# lorelei_B_v1_1.net
KiCad netlist of a schematic drawn in EAGLE
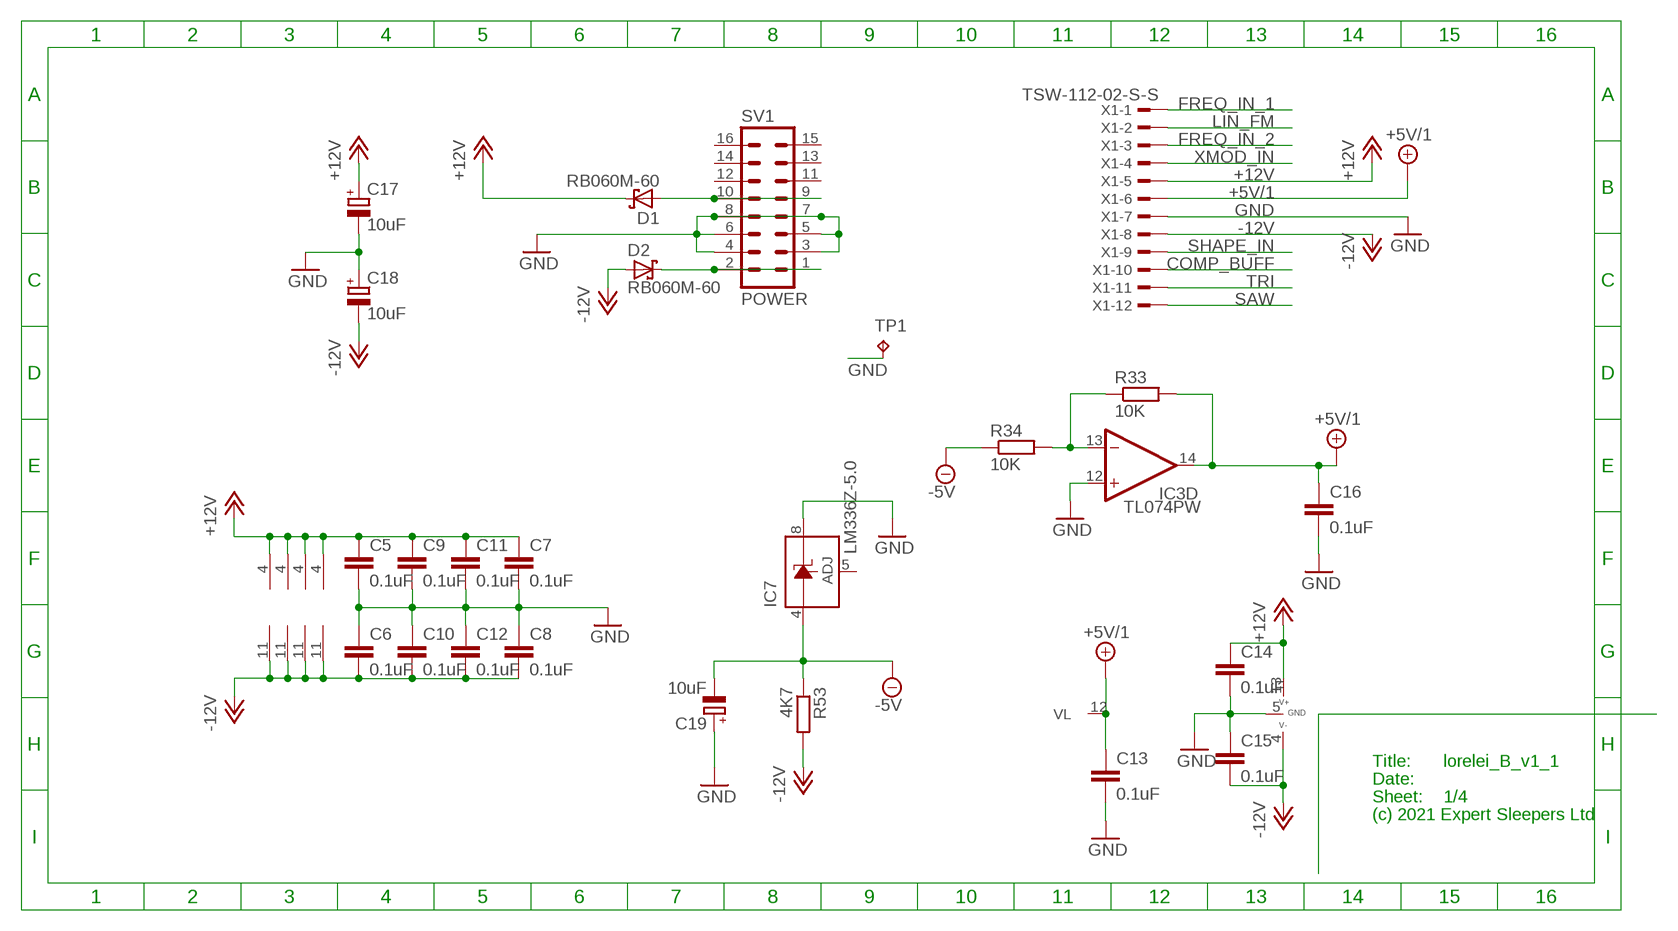
[diagram p0: schematic, sheet 1]
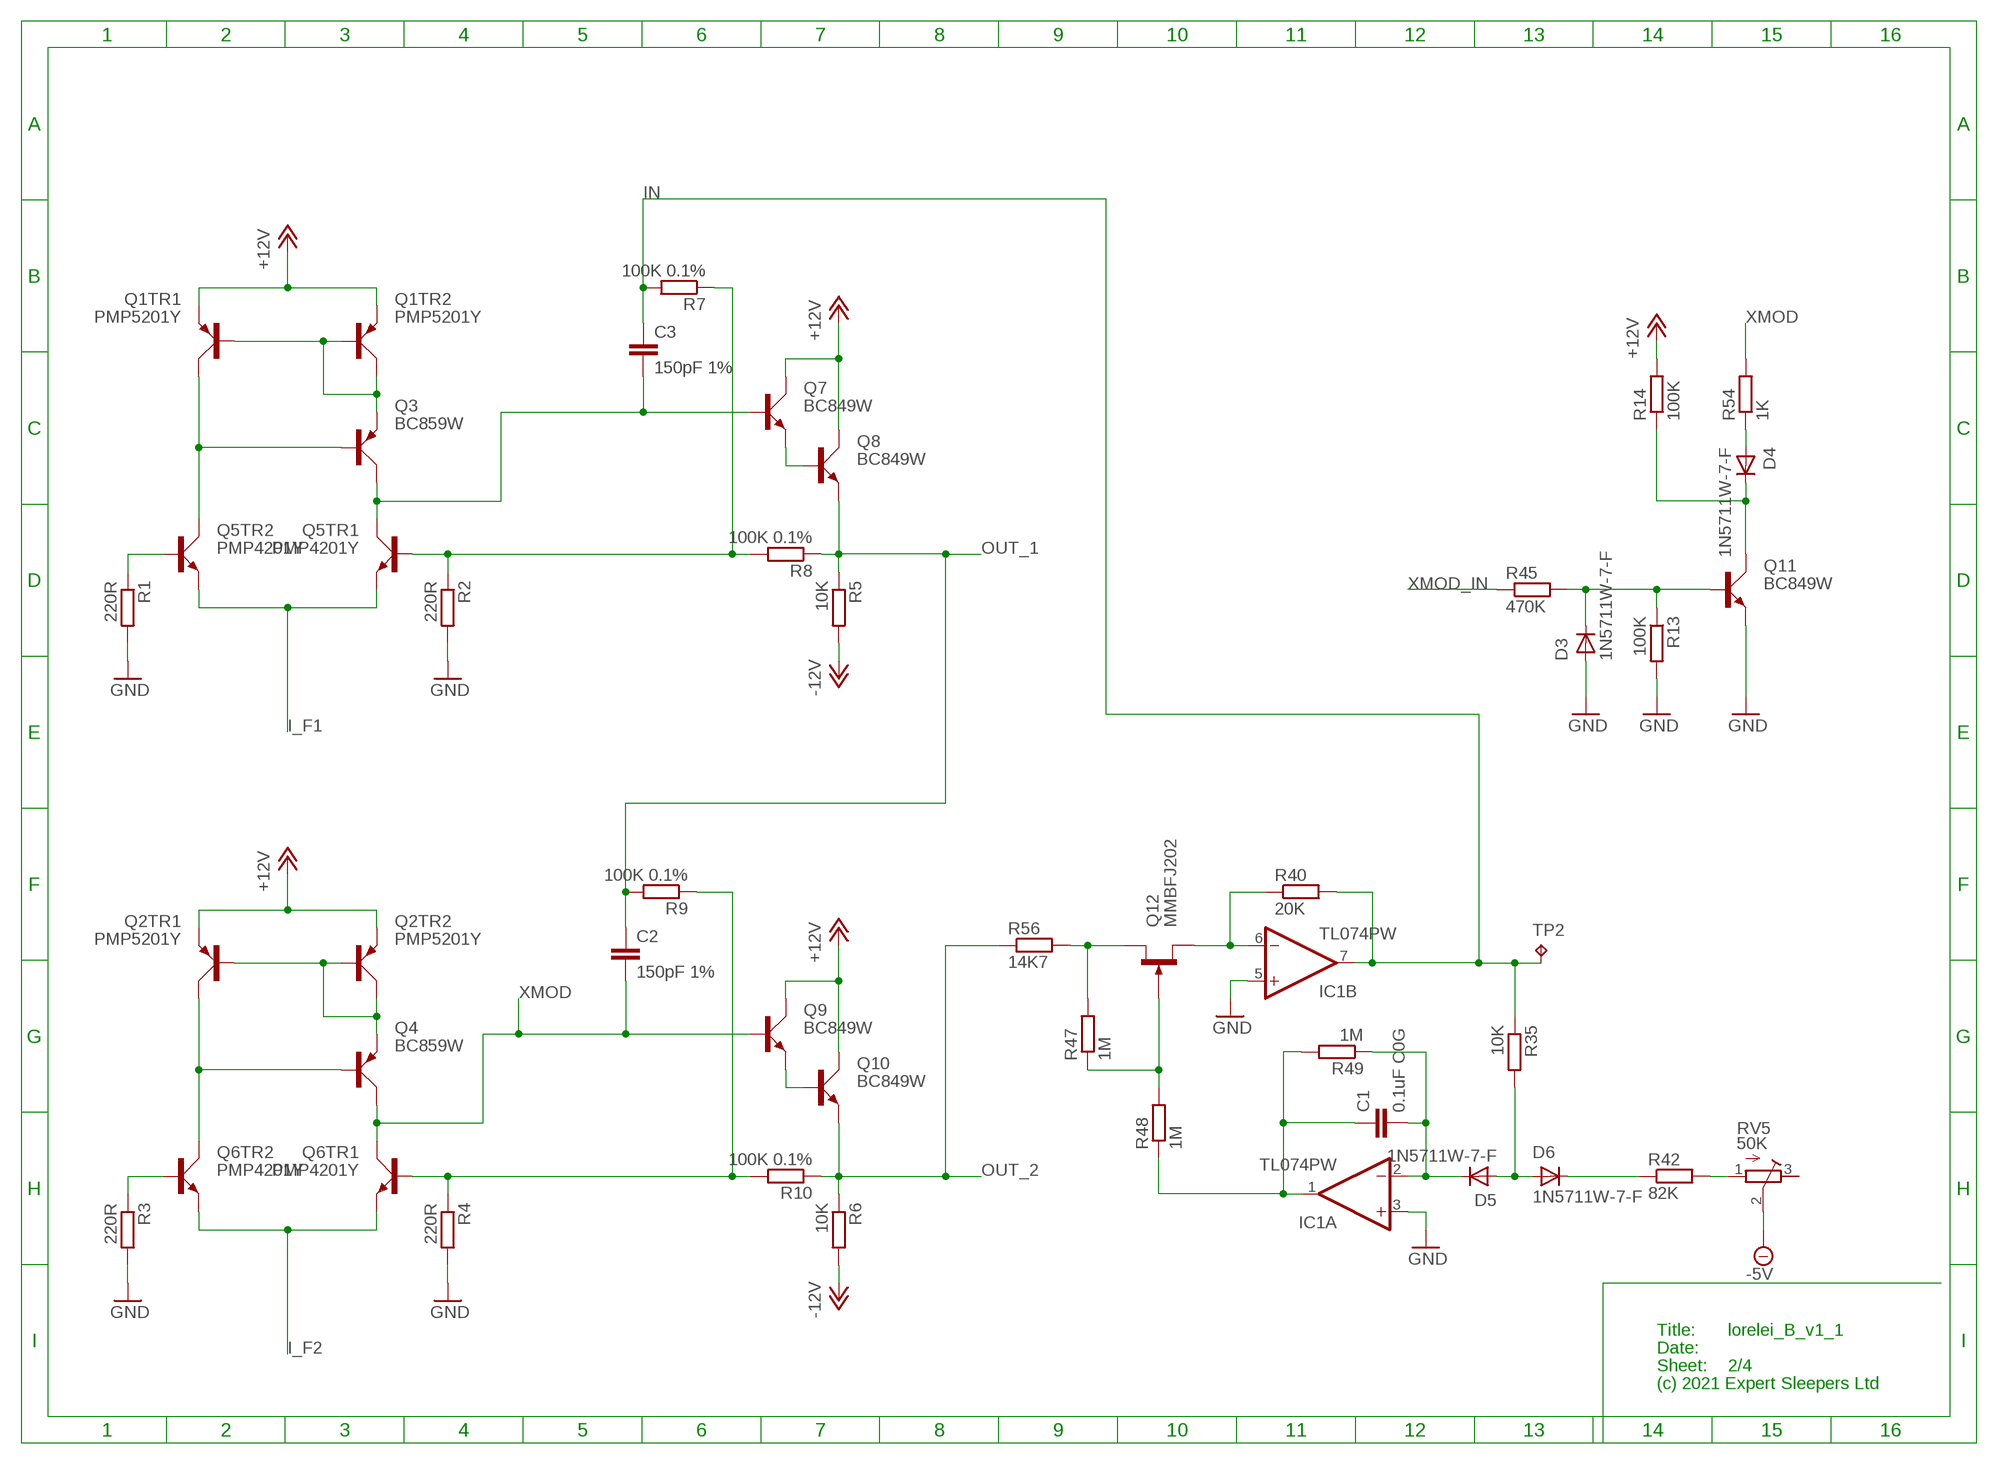
[diagram p1: schematic, sheet 2]
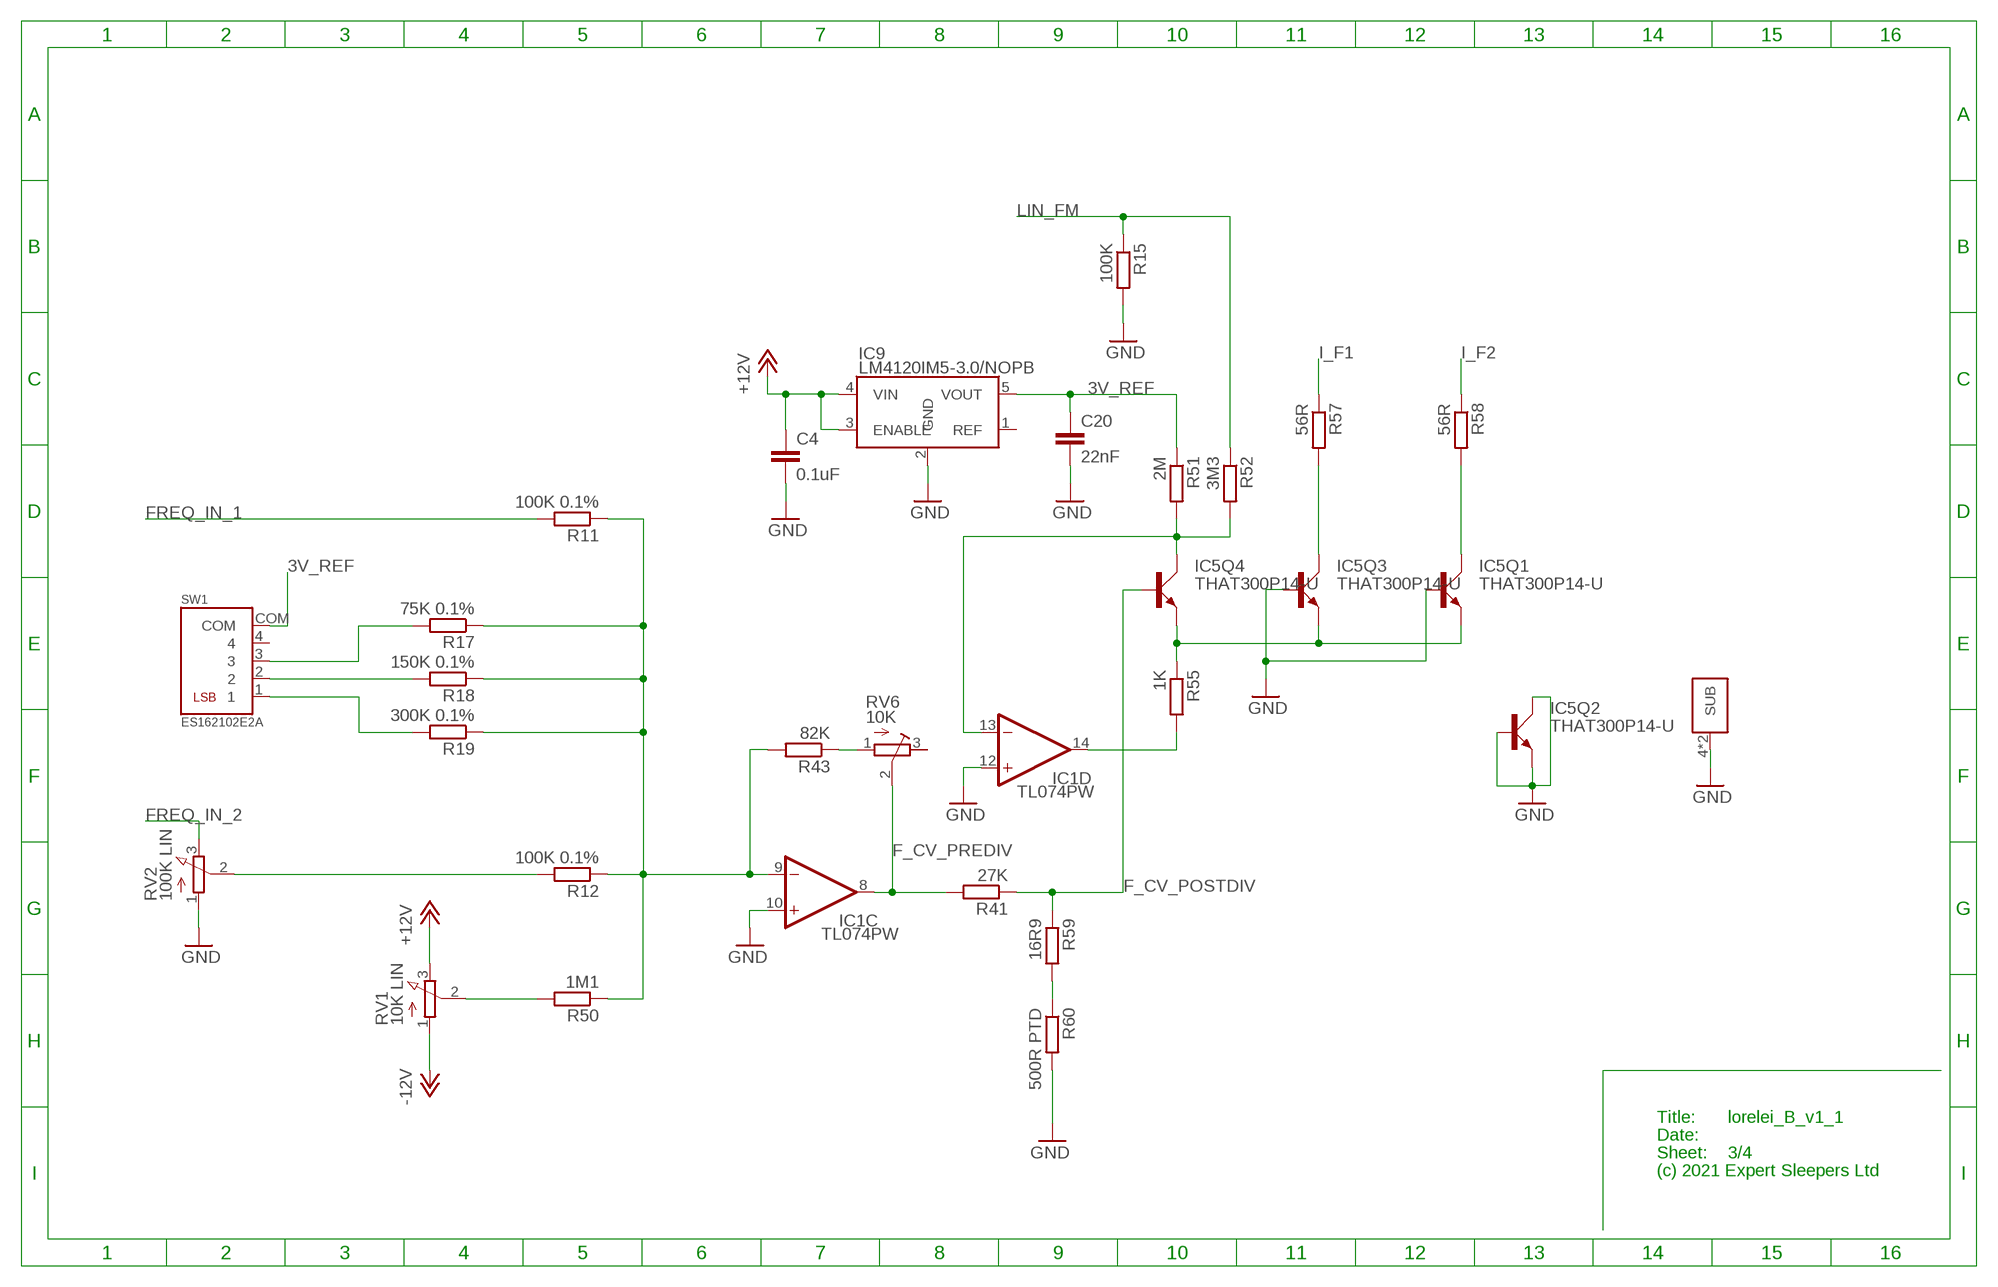
[diagram p2: schematic, sheet 3]
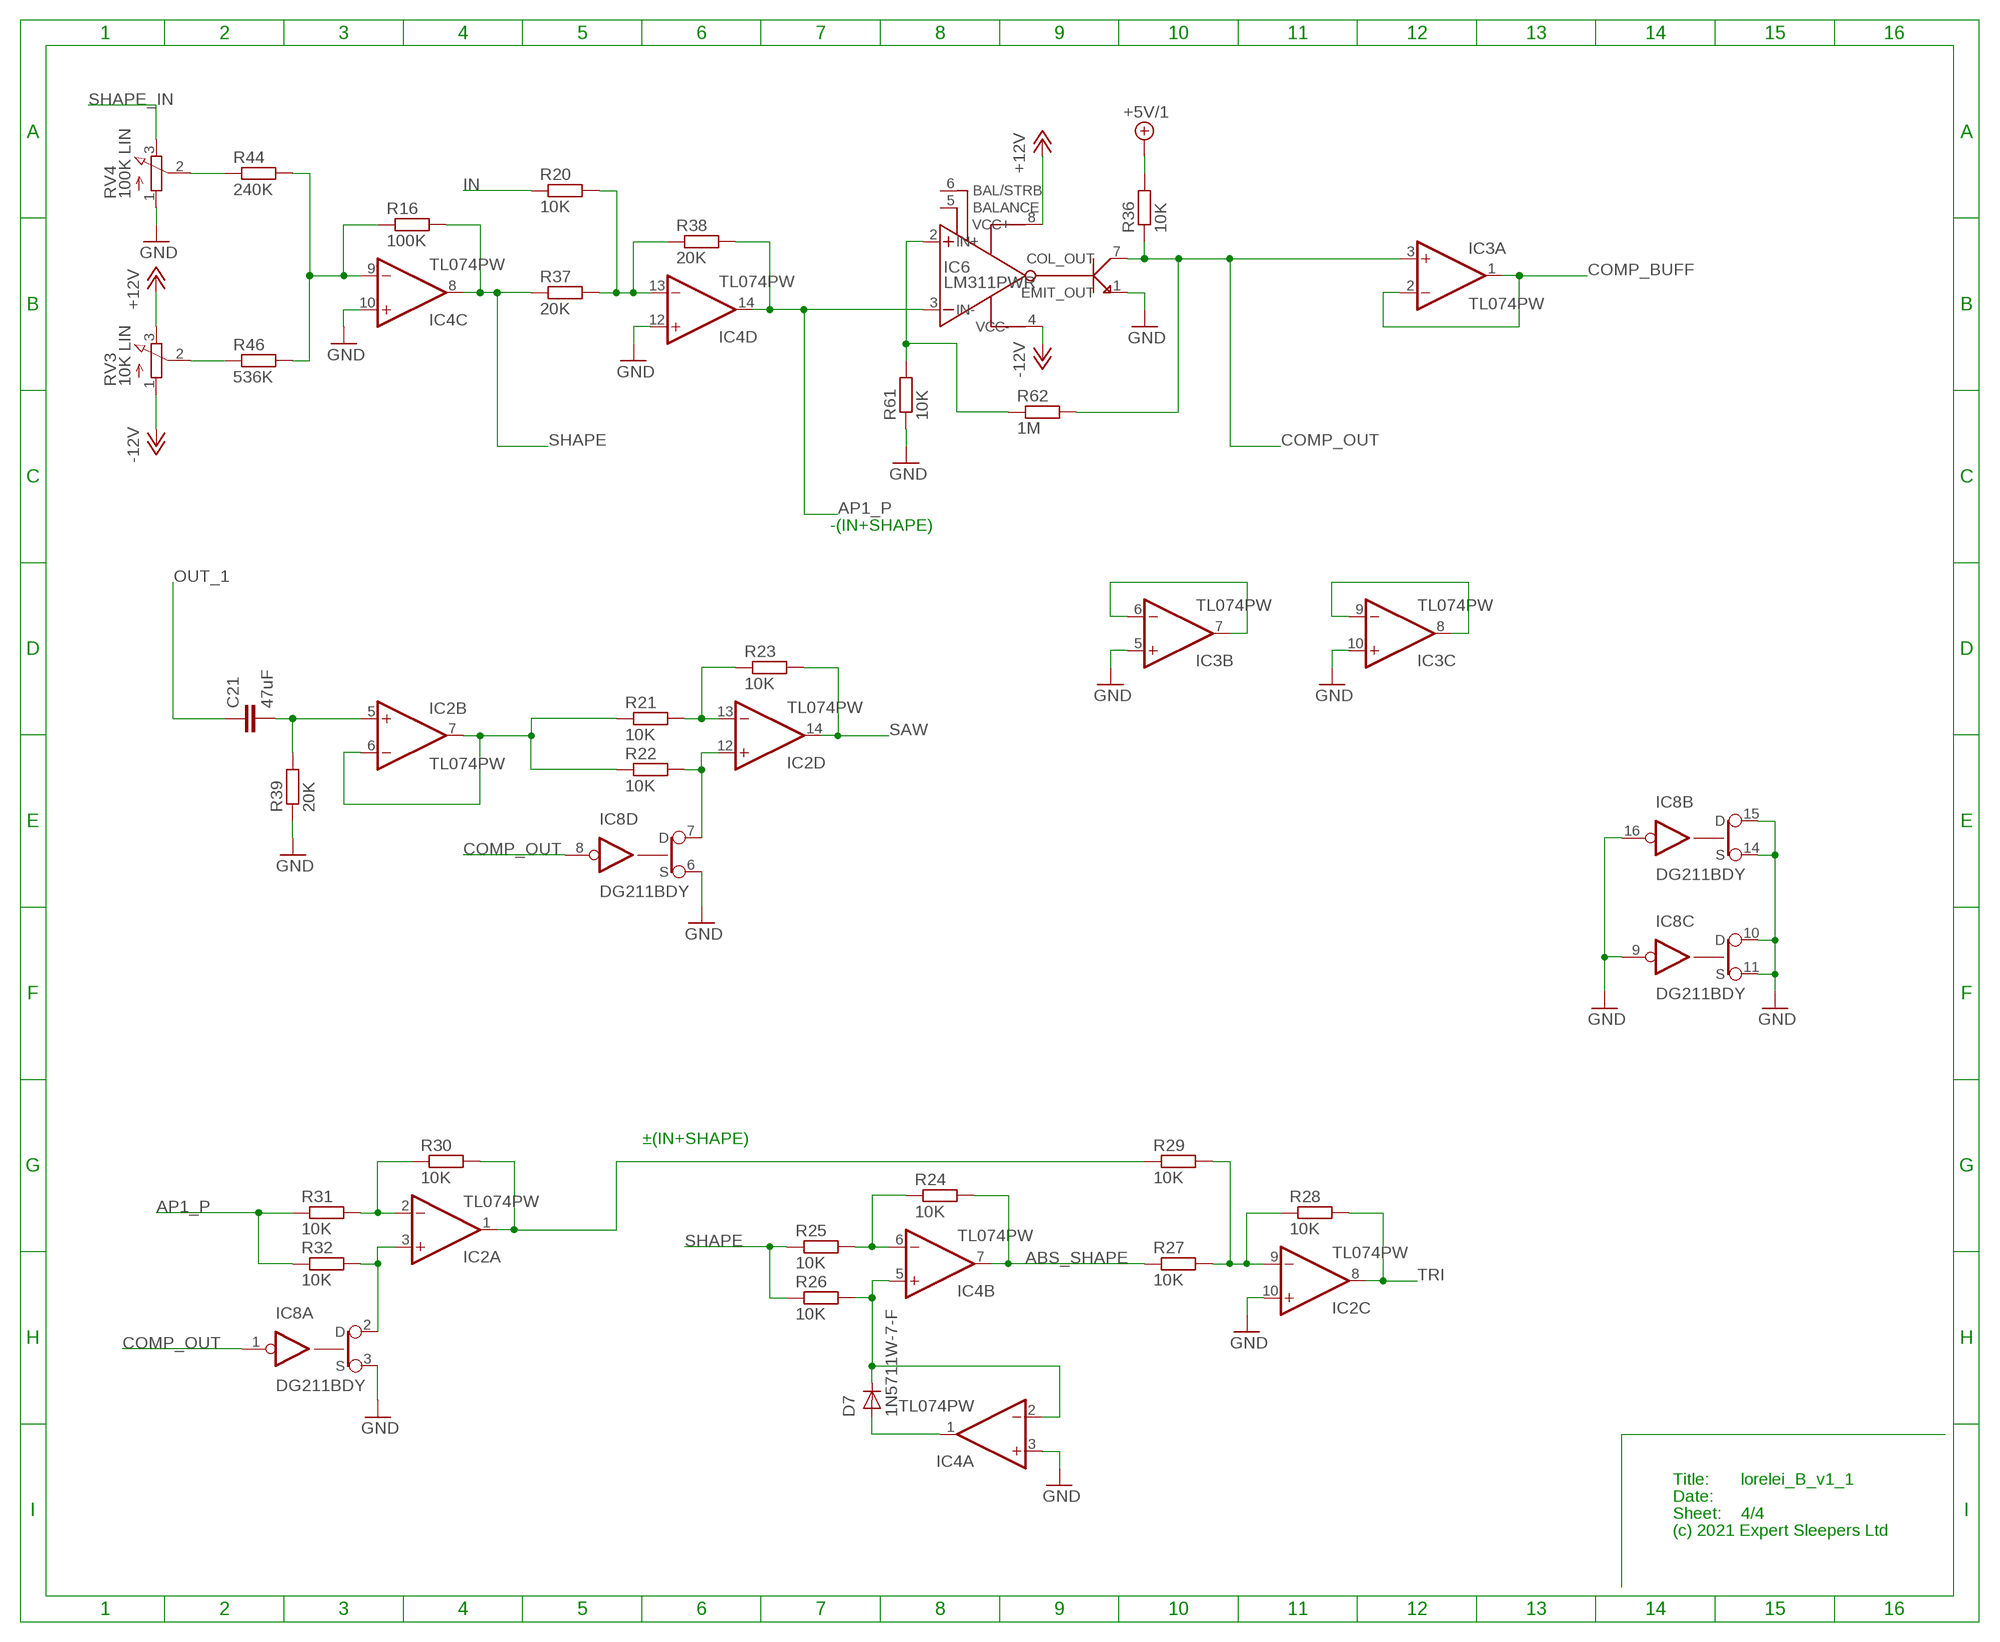
[diagram p3: schematic, sheet 4]

(export (version "E")
  (design (tool "Eeschema 10.0.6"))
  (components
    (comp (ref "C4")
      (value "0.1uF")
      (footprint "eagle-import:C0402")
      (libsource (lib "eagle-import") (part "C-EUC0402"))
    )
    (comp (ref "C20")
      (value "22nF")
      (footprint "eagle-import:C0402")
      (libsource (lib "eagle-import") (part "C-EUC0402"))
    )
    (comp (ref "IC1")
      (value "TL074PW")
      (footprint "eagle-import:PW_R-PDSO-G14")
      (libsource (lib "eagle-import") (part "TL074PW"))
    )
    (comp (ref "IC5")
      (value "THAT300P14-U")
      (footprint "eagle-import:DIL14")
      (libsource (lib "eagle-import") (part "THAT300P14-U"))
    )
    (comp (ref "IC9")
      (value "LM4120IM5-3.0/NOPB")
      (footprint "eagle-import:SOT95P280X145-5N")
      (fields
        (field (name "ARROW_PART_NUMBER") "LM4120IM5-5.0/NOPB")
        (field (name "MOUSER_PART_NUMBER") "926-LM4120IM550NOPB")
      )
      (libsource (lib "eagle-import") (part "LM4120IM5-5.0_NOPB"))
    )
    (comp (ref "R11")
      (value "100K 0.1%")
      (footprint "eagle-import:R0603")
      (libsource (lib "eagle-import") (part "R-EU_R0603"))
    )
    (comp (ref "R12")
      (value "100K 0.1%")
      (footprint "eagle-import:R0603")
      (libsource (lib "eagle-import") (part "R-EU_R0603"))
    )
    (comp (ref "R15")
      (value "100K")
      (footprint "eagle-import:R0603")
      (libsource (lib "eagle-import") (part "R-EU_R0603"))
    )
    (comp (ref "R17")
      (value "75K 0.1%")
      (footprint "eagle-import:R0603")
      (libsource (lib "eagle-import") (part "R-EU_R0603"))
    )
    (comp (ref "R18")
      (value "150K 0.1%")
      (footprint "eagle-import:R0603")
      (libsource (lib "eagle-import") (part "R-EU_R0603"))
    )
    (comp (ref "R19")
      (value "300K 0.1%")
      (footprint "eagle-import:R0603")
      (libsource (lib "eagle-import") (part "R-EU_R0603"))
    )
    (comp (ref "R41")
      (value "27K")
      (footprint "eagle-import:R0603")
      (libsource (lib "eagle-import") (part "R-EU_R0603"))
    )
    (comp (ref "R43")
      (value "82K")
      (footprint "eagle-import:R0603")
      (libsource (lib "eagle-import") (part "R-EU_R0603"))
    )
    (comp (ref "R50")
      (value "1M1")
      (footprint "eagle-import:R0603")
      (libsource (lib "eagle-import") (part "R-EU_R0603"))
    )
    (comp (ref "R51")
      (value "2M")
      (footprint "eagle-import:R0603")
      (libsource (lib "eagle-import") (part "R-EU_R0603"))
    )
    (comp (ref "R52")
      (value "3M3")
      (footprint "eagle-import:R0603")
      (libsource (lib "eagle-import") (part "R-EU_R0603"))
    )
    (comp (ref "R55")
      (value "1K")
      (footprint "eagle-import:R0603")
      (libsource (lib "eagle-import") (part "R-EU_R0603"))
    )
    (comp (ref "R57")
      (value "56R")
      (footprint "eagle-import:R0603")
      (libsource (lib "eagle-import") (part "R-EU_R0603"))
    )
    (comp (ref "R58")
      (value "56R")
      (footprint "eagle-import:R0603")
      (libsource (lib "eagle-import") (part "R-EU_R0603"))
    )
    (comp (ref "R59")
      (value "16R9")
      (footprint "eagle-import:R0603")
      (libsource (lib "eagle-import") (part "R-EU_R0603"))
    )
    (comp (ref "R60")
      (value "500R PTD")
      (footprint "eagle-import:R0805")
      (libsource (lib "eagle-import") (part "R-EU_R0805"))
    )
    (comp (ref "RV1")
      (value "10K LIN")
      (footprint "eagle-import:RD1610NOA0X")
      (libsource (lib "eagle-import") (part "RD1610NOA0X"))
    )
    (comp (ref "RV2")
      (value "100K LIN")
      (footprint "eagle-import:RD1610NOA0X")
      (libsource (lib "eagle-import") (part "RD1610NOA0X"))
    )
    (comp (ref "RV6")
      (value "10K")
      (footprint "eagle-import:RTRIM3296W")
      (libsource (lib "eagle-import") (part "T93YA"))
    )
    (comp (ref "SW1")
      (value "ES162102E2A")
      (footprint "eagle-import:ES162102E2A")
      (libsource (lib "eagle-import") (part "ES162102E2A"))
    )
    (comp (ref "C1")
      (value "0.1uF C0G")
      (footprint "eagle-import:C1206")
      (libsource (lib "eagle-import") (part "C-EUC1206"))
    )
    (comp (ref "C2")
      (value "150pF 1%")
      (footprint "eagle-import:C0805")
      (libsource (lib "eagle-import") (part "C-EUC0805"))
    )
    (comp (ref "C3")
      (value "150pF 1%")
      (footprint "eagle-import:C0805")
      (libsource (lib "eagle-import") (part "C-EUC0805"))
    )
    (comp (ref "D3")
      (value "1N5711W-7-F")
      (footprint "eagle-import:SOD123")
      (libsource (lib "eagle-import") (part "1N4148W"))
    )
    (comp (ref "D4")
      (value "1N5711W-7-F")
      (footprint "eagle-import:SOD123")
      (libsource (lib "eagle-import") (part "1N4148W"))
    )
    (comp (ref "D5")
      (value "1N5711W-7-F")
      (footprint "eagle-import:SOD123")
      (libsource (lib "eagle-import") (part "1N4148W"))
    )
    (comp (ref "D6")
      (value "1N5711W-7-F")
      (footprint "eagle-import:SOD123")
      (libsource (lib "eagle-import") (part "1N4148W"))
    )
    (comp (ref "Q1")
      (value "PMP5201Y")
      (footprint "eagle-import:SOT65P210X110-6N")
      (fields
        (field (name "ARROW_PART_NUMBER") "PMP5201Y,135")
        (field (name "MOUSER_PART_NUMBER") "771-PMP5201Y135")
      )
      (libsource (lib "eagle-import") (part "PMP5201Y"))
    )
    (comp (ref "Q2")
      (value "PMP5201Y")
      (footprint "eagle-import:SOT65P210X110-6N")
      (fields
        (field (name "ARROW_PART_NUMBER") "PMP5201Y,135")
        (field (name "MOUSER_PART_NUMBER") "771-PMP5201Y135")
      )
      (libsource (lib "eagle-import") (part "PMP5201Y"))
    )
    (comp (ref "Q3")
      (value "BC859W")
      (footprint "eagle-import:SOT323")
      (libsource (lib "eagle-import") (part "BC859W"))
    )
    (comp (ref "Q4")
      (value "BC859W")
      (footprint "eagle-import:SOT323")
      (libsource (lib "eagle-import") (part "BC859W"))
    )
    (comp (ref "Q5")
      (value "PMP4201Y")
      (footprint "eagle-import:SOT65P210X110-6N")
      (fields
        (field (name "ARROW_PART_NUMBER") "PMP4201Y,135")
        (field (name "MOUSER_PART_NUMBER") "771-PMP4201Y135")
      )
      (libsource (lib "eagle-import") (part "PMP4201Y"))
    )
    (comp (ref "Q6")
      (value "PMP4201Y")
      (footprint "eagle-import:SOT65P210X110-6N")
      (fields
        (field (name "ARROW_PART_NUMBER") "PMP4201Y,135")
        (field (name "MOUSER_PART_NUMBER") "771-PMP4201Y135")
      )
      (libsource (lib "eagle-import") (part "PMP4201Y"))
    )
    (comp (ref "Q7")
      (value "BC849W")
      (footprint "eagle-import:SOT323")
      (libsource (lib "eagle-import") (part "BC849W"))
    )
    (comp (ref "Q8")
      (value "BC849W")
      (footprint "eagle-import:SOT323")
      (libsource (lib "eagle-import") (part "BC849W"))
    )
    (comp (ref "Q9")
      (value "BC849W")
      (footprint "eagle-import:SOT323")
      (libsource (lib "eagle-import") (part "BC849W"))
    )
    (comp (ref "Q10")
      (value "BC849W")
      (footprint "eagle-import:SOT323")
      (libsource (lib "eagle-import") (part "BC849W"))
    )
    (comp (ref "Q11")
      (value "BC849W")
      (footprint "eagle-import:SOT323")
      (libsource (lib "eagle-import") (part "BC849W"))
    )
    (comp (ref "Q12")
      (value "MMBFJ202")
      (footprint "eagle-import:SOT23")
      (libsource (lib "eagle-import") (part "MMBFJ3"))
    )
    (comp (ref "R1")
      (value "220R")
      (footprint "eagle-import:R0603")
      (libsource (lib "eagle-import") (part "R-EU_R0603"))
    )
    (comp (ref "R2")
      (value "220R")
      (footprint "eagle-import:R0603")
      (libsource (lib "eagle-import") (part "R-EU_R0603"))
    )
    (comp (ref "R3")
      (value "220R")
      (footprint "eagle-import:R0603")
      (libsource (lib "eagle-import") (part "R-EU_R0603"))
    )
    (comp (ref "R4")
      (value "220R")
      (footprint "eagle-import:R0603")
      (libsource (lib "eagle-import") (part "R-EU_R0603"))
    )
    (comp (ref "R5")
      (value "10K")
      (footprint "eagle-import:R0603")
      (libsource (lib "eagle-import") (part "R-EU_R0603"))
    )
    (comp (ref "R6")
      (value "10K")
      (footprint "eagle-import:R0603")
      (libsource (lib "eagle-import") (part "R-EU_R0603"))
    )
    (comp (ref "R7")
      (value "100K 0.1%")
      (footprint "eagle-import:R0603")
      (libsource (lib "eagle-import") (part "R-EU_R0603"))
    )
    (comp (ref "R8")
      (value "100K 0.1%")
      (footprint "eagle-import:R0603")
      (libsource (lib "eagle-import") (part "R-EU_R0603"))
    )
    (comp (ref "R9")
      (value "100K 0.1%")
      (footprint "eagle-import:R0603")
      (libsource (lib "eagle-import") (part "R-EU_R0603"))
    )
    (comp (ref "R10")
      (value "100K 0.1%")
      (footprint "eagle-import:R0603")
      (libsource (lib "eagle-import") (part "R-EU_R0603"))
    )
    (comp (ref "R13")
      (value "100K")
      (footprint "eagle-import:R0603")
      (libsource (lib "eagle-import") (part "R-EU_R0603"))
    )
    (comp (ref "R14")
      (value "100K")
      (footprint "eagle-import:R0603")
      (libsource (lib "eagle-import") (part "R-EU_R0603"))
    )
    (comp (ref "R35")
      (value "10K")
      (footprint "eagle-import:R0603")
      (libsource (lib "eagle-import") (part "R-EU_R0603"))
    )
    (comp (ref "R40")
      (value "20K")
      (footprint "eagle-import:R0603")
      (libsource (lib "eagle-import") (part "R-EU_R0603"))
    )
    (comp (ref "R42")
      (value "82K")
      (footprint "eagle-import:R0603")
      (libsource (lib "eagle-import") (part "R-EU_R0603"))
    )
    (comp (ref "R45")
      (value "470K")
      (footprint "eagle-import:R0603")
      (libsource (lib "eagle-import") (part "R-EU_R0603"))
    )
    (comp (ref "R47")
      (value "1M")
      (footprint "eagle-import:R0603")
      (libsource (lib "eagle-import") (part "R-EU_R0603"))
    )
    (comp (ref "R48")
      (value "1M")
      (footprint "eagle-import:R0603")
      (libsource (lib "eagle-import") (part "R-EU_R0603"))
    )
    (comp (ref "R49")
      (value "1M")
      (footprint "eagle-import:R0603")
      (libsource (lib "eagle-import") (part "R-EU_R0603"))
    )
    (comp (ref "R54")
      (value "1K")
      (footprint "eagle-import:R0603")
      (libsource (lib "eagle-import") (part "R-EU_R0603"))
    )
    (comp (ref "R56")
      (value "14K7")
      (footprint "eagle-import:R0603")
      (libsource (lib "eagle-import") (part "R-EU_R0603"))
    )
    (comp (ref "RV5")
      (value "50K")
      (footprint "eagle-import:TC33X")
      (libsource (lib "eagle-import") (part "TC33X"))
    )
    (comp (ref "TP2")
      (value "RA2")
      (footprint "eagle-import:P1-13")
      (libsource (lib "eagle-import") (part "TPPAD1-13"))
    )
    (comp (ref "C21")
      (value "47uF")
      (footprint "eagle-import:C1206")
      (libsource (lib "eagle-import") (part "C-EUC1206"))
    )
    (comp (ref "D7")
      (value "1N5711W-7-F")
      (footprint "eagle-import:SOD123")
      (libsource (lib "eagle-import") (part "1N4148W"))
    )
    (comp (ref "IC2")
      (value "TL074PW")
      (footprint "eagle-import:PW_R-PDSO-G14")
      (libsource (lib "eagle-import") (part "TL074PW"))
    )
    (comp (ref "IC3")
      (value "TL074PW")
      (footprint "eagle-import:PW_R-PDSO-G14")
      (libsource (lib "eagle-import") (part "TL074PW"))
    )
    (comp (ref "IC4")
      (value "TL074PW")
      (footprint "eagle-import:PW_R-PDSO-G14")
      (libsource (lib "eagle-import") (part "TL074PW"))
    )
    (comp (ref "IC6")
      (value "LM311PWR")
      (footprint "eagle-import:SOP65P640X120-8N")
      (fields (field (name "MOUSER_PART_NUMBER") "595-LM311PWR"))
      (libsource (lib "eagle-import") (part "LM311PWR"))
    )
    (comp (ref "IC8")
      (value "DG211BDY")
      (footprint "eagle-import:SO16")
      (libsource (lib "eagle-import") (part "DG211CJD"))
    )
    (comp (ref "R16")
      (value "100K")
      (footprint "eagle-import:R0603")
      (libsource (lib "eagle-import") (part "R-EU_R0603"))
    )
    (comp (ref "R20")
      (value "10K")
      (footprint "eagle-import:R0603")
      (libsource (lib "eagle-import") (part "R-EU_R0603"))
    )
    (comp (ref "R21")
      (value "10K")
      (footprint "eagle-import:R0603")
      (libsource (lib "eagle-import") (part "R-EU_R0603"))
    )
    (comp (ref "R22")
      (value "10K")
      (footprint "eagle-import:R0603")
      (libsource (lib "eagle-import") (part "R-EU_R0603"))
    )
    (comp (ref "R23")
      (value "10K")
      (footprint "eagle-import:R0603")
      (libsource (lib "eagle-import") (part "R-EU_R0603"))
    )
    (comp (ref "R24")
      (value "10K")
      (footprint "eagle-import:R0603")
      (libsource (lib "eagle-import") (part "R-EU_R0603"))
    )
    (comp (ref "R25")
      (value "10K")
      (footprint "eagle-import:R0603")
      (libsource (lib "eagle-import") (part "R-EU_R0603"))
    )
    (comp (ref "R26")
      (value "10K")
      (footprint "eagle-import:R0603")
      (libsource (lib "eagle-import") (part "R-EU_R0603"))
    )
    (comp (ref "R27")
      (value "10K")
      (footprint "eagle-import:R0603")
      (libsource (lib "eagle-import") (part "R-EU_R0603"))
    )
    (comp (ref "R28")
      (value "10K")
      (footprint "eagle-import:R0603")
      (libsource (lib "eagle-import") (part "R-EU_R0603"))
    )
    (comp (ref "R29")
      (value "10K")
      (footprint "eagle-import:R0603")
      (libsource (lib "eagle-import") (part "R-EU_R0603"))
    )
    (comp (ref "R30")
      (value "10K")
      (footprint "eagle-import:R0603")
      (libsource (lib "eagle-import") (part "R-EU_R0603"))
    )
    (comp (ref "R31")
      (value "10K")
      (footprint "eagle-import:R0603")
      (libsource (lib "eagle-import") (part "R-EU_R0603"))
    )
    (comp (ref "R32")
      (value "10K")
      (footprint "eagle-import:R0603")
      (libsource (lib "eagle-import") (part "R-EU_R0603"))
    )
    (comp (ref "R36")
      (value "10K")
      (footprint "eagle-import:R0603")
      (libsource (lib "eagle-import") (part "R-EU_R0603"))
    )
    (comp (ref "R37")
      (value "20K")
      (footprint "eagle-import:R0603")
      (libsource (lib "eagle-import") (part "R-EU_R0603"))
    )
    (comp (ref "R38")
      (value "20K")
      (footprint "eagle-import:R0603")
      (libsource (lib "eagle-import") (part "R-EU_R0603"))
    )
    (comp (ref "R39")
      (value "20K")
      (footprint "eagle-import:R0603")
      (libsource (lib "eagle-import") (part "R-EU_R0603"))
    )
    (comp (ref "R44")
      (value "240K")
      (footprint "eagle-import:R0603")
      (libsource (lib "eagle-import") (part "R-EU_R0603"))
    )
    (comp (ref "R46")
      (value "536K")
      (footprint "eagle-import:R0603")
      (libsource (lib "eagle-import") (part "R-EU_R0603"))
    )
    (comp (ref "R61")
      (value "10K")
      (footprint "eagle-import:R0603")
      (libsource (lib "eagle-import") (part "R-EU_R0603"))
    )
    (comp (ref "R62")
      (value "1M")
      (footprint "eagle-import:R0603")
      (libsource (lib "eagle-import") (part "R-EU_R0603"))
    )
    (comp (ref "RV3")
      (value "10K LIN")
      (footprint "eagle-import:RD1610NOA0X")
      (libsource (lib "eagle-import") (part "RD1610NOA0X"))
    )
    (comp (ref "RV4")
      (value "100K LIN")
      (footprint "eagle-import:RD1610NOA0X")
      (libsource (lib "eagle-import") (part "RD1610NOA0X"))
    )
    (comp (ref "C5")
      (value "0.1uF")
      (footprint "eagle-import:C0402")
      (libsource (lib "eagle-import") (part "C-EUC0402"))
    )
    (comp (ref "C6")
      (value "0.1uF")
      (footprint "eagle-import:C0402")
      (libsource (lib "eagle-import") (part "C-EUC0402"))
    )
    (comp (ref "C7")
      (value "0.1uF")
      (footprint "eagle-import:C0402")
      (libsource (lib "eagle-import") (part "C-EUC0402"))
    )
    (comp (ref "C8")
      (value "0.1uF")
      (footprint "eagle-import:C0402")
      (libsource (lib "eagle-import") (part "C-EUC0402"))
    )
    (comp (ref "C9")
      (value "0.1uF")
      (footprint "eagle-import:C0402")
      (libsource (lib "eagle-import") (part "C-EUC0402"))
    )
    (comp (ref "C10")
      (value "0.1uF")
      (footprint "eagle-import:C0402")
      (libsource (lib "eagle-import") (part "C-EUC0402"))
    )
    (comp (ref "C11")
      (value "0.1uF")
      (footprint "eagle-import:C0402")
      (libsource (lib "eagle-import") (part "C-EUC0402"))
    )
    (comp (ref "C12")
      (value "0.1uF")
      (footprint "eagle-import:C0402")
      (libsource (lib "eagle-import") (part "C-EUC0402"))
    )
    (comp (ref "C13")
      (value "0.1uF")
      (footprint "eagle-import:C0402")
      (libsource (lib "eagle-import") (part "C-EUC0402"))
    )
    (comp (ref "C14")
      (value "0.1uF")
      (footprint "eagle-import:C0402")
      (libsource (lib "eagle-import") (part "C-EUC0402"))
    )
    (comp (ref "C15")
      (value "0.1uF")
      (footprint "eagle-import:C0402")
      (libsource (lib "eagle-import") (part "C-EUC0402"))
    )
    (comp (ref "C16")
      (value "0.1uF")
      (footprint "eagle-import:C0402")
      (libsource (lib "eagle-import") (part "C-EUC0402"))
    )
    (comp (ref "C17")
      (value "10uF")
      (footprint "eagle-import:UD-4X5,8_NICHICON")
      (libsource (lib "eagle-import") (part "CPOL-EUUD-4X5,8"))
    )
    (comp (ref "C18")
      (value "10uF")
      (footprint "eagle-import:UD-4X5,8_NICHICON")
      (libsource (lib "eagle-import") (part "CPOL-EUUD-4X5,8"))
    )
    (comp (ref "C19")
      (value "10uF")
      (footprint "eagle-import:UD-4X5,8_NICHICON")
      (libsource (lib "eagle-import") (part "CPOL-EUUD-4X5,8"))
    )
    (comp (ref "D1")
      (value "RB060M-60")
      (footprint "eagle-import:SOD123FL")
      (libsource (lib "eagle-import") (part "RB060M-60"))
    )
    (comp (ref "D2")
      (value "RB060M-60")
      (footprint "eagle-import:SOD123FL")
      (libsource (lib "eagle-import") (part "RB060M-60"))
    )
    (comp (ref "IC7")
      (value "LM336Z-5.0")
      (footprint "eagle-import:SO08")
      (libsource (lib "eagle-import") (part "LM336D"))
    )
    (comp (ref "R33")
      (value "10K")
      (footprint "eagle-import:R0603")
      (libsource (lib "eagle-import") (part "R-EU_R0603"))
    )
    (comp (ref "R34")
      (value "10K")
      (footprint "eagle-import:R0603")
      (libsource (lib "eagle-import") (part "R-EU_R0603"))
    )
    (comp (ref "R53")
      (value "4K7")
      (footprint "eagle-import:R0603")
      (libsource (lib "eagle-import") (part "R-EU_R0603"))
    )
    (comp (ref "SV1")
      (value "POWER")
      (footprint "eagle-import:ML16")
      (libsource (lib "eagle-import") (part "ML16"))
    )
    (comp (ref "TP1")
      (value "RA2")
      (footprint "eagle-import:P1-13")
      (libsource (lib "eagle-import") (part "TPPAD1-13"))
    )
    (comp (ref "X1")
      (value "TSW-112-02-S-S")
      (footprint "eagle-import:TSW-112-02-S-S")
      (libsource (lib "eagle-import") (part "TSW-112-02-S-S"))
    )
  )
  (nets
    (net (code "1") (name "+5V{slash}1") (class "Default")
      (node (ref "C13") (pin "1") (pinfunction "1_1") (pintype "passive"))
      (node (ref "C16") (pin "1") (pinfunction "1_1") (pintype "passive"))
      (node (ref "IC3") (pin "14") (pinfunction "OUT_14") (pintype "output"))
      (node (ref "IC8") (pin "12") (pinfunction "VL_12") (pintype "input"))
      (node (ref "R33") (pin "2") (pinfunction "2_2") (pintype "passive"))
      (node (ref "R36") (pin "2") (pinfunction "2_2") (pintype "passive"))
      (node (ref "X1") (pin "6") (pinfunction "1_6") (pintype "passive"))
    )
    (net (code "2") (name "+12V") (class "Default")
      (node (ref "C11") (pin "1") (pinfunction "1_1") (pintype "passive"))
      (node (ref "C14") (pin "1") (pinfunction "1_1") (pintype "passive"))
      (node (ref "C17") (pin "+") (pinfunction "+_+") (pintype "passive"))
      (node (ref "C4") (pin "1") (pinfunction "1_1") (pintype "passive"))
      (node (ref "C5") (pin "1") (pinfunction "1_1") (pintype "passive"))
      (node (ref "C7") (pin "1") (pinfunction "1_1") (pintype "passive"))
      (node (ref "C9") (pin "1") (pinfunction "1_1") (pintype "passive"))
      (node (ref "D1") (pin "C") (pinfunction "C_C") (pintype "passive"))
      (node (ref "IC1") (pin "4") (pinfunction "V+_4") (pintype "power_in"))
      (node (ref "IC2") (pin "4") (pinfunction "V+_4") (pintype "power_in"))
      (node (ref "IC3") (pin "4") (pinfunction "V+_4") (pintype "power_in"))
      (node (ref "IC4") (pin "4") (pinfunction "V+_4") (pintype "power_in"))
      (node (ref "IC6") (pin "8") (pinfunction "VCC+_8") (pintype "power_in"))
      (node (ref "IC8") (pin "13") (pinfunction "V+_13") (pintype "power_in"))
      (node (ref "IC9") (pin "3") (pinfunction "ENABLE_3") (pintype "input"))
      (node (ref "IC9") (pin "4") (pinfunction "VIN_4") (pintype "power_in"))
      (node (ref "Q1") (pin "4") (pinfunction "E_4") (pintype "passive"))
      (node (ref "Q1") (pin "5") (pinfunction "E_5") (pintype "passive"))
      (node (ref "Q10") (pin "3") (pinfunction "C_3") (pintype "passive"))
      (node (ref "Q2") (pin "4") (pinfunction "E_4") (pintype "passive"))
      (node (ref "Q2") (pin "5") (pinfunction "E_5") (pintype "passive"))
      (node (ref "Q7") (pin "3") (pinfunction "C_3") (pintype "passive"))
      (node (ref "Q8") (pin "3") (pinfunction "C_3") (pintype "passive"))
      (node (ref "Q9") (pin "3") (pinfunction "C_3") (pintype "passive"))
      (node (ref "R14") (pin "2") (pinfunction "2_2") (pintype "passive"))
      (node (ref "RV1") (pin "3") (pinfunction "E_3") (pintype "passive"))
      (node (ref "RV3") (pin "3") (pinfunction "E_3") (pintype "passive"))
      (node (ref "X1") (pin "5") (pinfunction "1_5") (pintype "passive"))
    )
    (net (code "3") (name "-5V") (class "Default")
      (node (ref "C19") (pin "-") (pinfunction "-_-") (pintype "passive"))
      (node (ref "IC7") (pin "4") (pinfunction "A_4") (pintype "input"))
      (node (ref "R34") (pin "1") (pinfunction "1_1") (pintype "passive"))
      (node (ref "R53") (pin "1") (pinfunction "1_1") (pintype "passive"))
      (node (ref "RV5") (pin "2") (pinfunction "S_2") (pintype "passive"))
    )
    (net (code "4") (name "-12V") (class "Default")
      (node (ref "C10") (pin "2") (pinfunction "2_2") (pintype "passive"))
      (node (ref "C12") (pin "2") (pinfunction "2_2") (pintype "passive"))
      (node (ref "C15") (pin "2") (pinfunction "2_2") (pintype "passive"))
      (node (ref "C18") (pin "-") (pinfunction "-_-") (pintype "passive"))
      (node (ref "C6") (pin "2") (pinfunction "2_2") (pintype "passive"))
      (node (ref "C8") (pin "2") (pinfunction "2_2") (pintype "passive"))
      (node (ref "D2") (pin "A") (pinfunction "A_A") (pintype "passive"))
      (node (ref "IC1") (pin "11") (pinfunction "V-_11") (pintype "power_in"))
      (node (ref "IC2") (pin "11") (pinfunction "V-_11") (pintype "power_in"))
      (node (ref "IC3") (pin "11") (pinfunction "V-_11") (pintype "power_in"))
      (node (ref "IC4") (pin "11") (pinfunction "V-_11") (pintype "power_in"))
      (node (ref "IC6") (pin "4") (pinfunction "VCC-_4") (pintype "power_in"))
      (node (ref "IC8") (pin "4") (pinfunction "V-_4") (pintype "power_in"))
      (node (ref "R5") (pin "2") (pinfunction "2_2") (pintype "passive"))
      (node (ref "R53") (pin "2") (pinfunction "2_2") (pintype "passive"))
      (node (ref "R6") (pin "2") (pinfunction "2_2") (pintype "passive"))
      (node (ref "RV1") (pin "1") (pinfunction "A_1") (pintype "passive"))
      (node (ref "RV3") (pin "1") (pinfunction "A_1") (pintype "passive"))
      (node (ref "X1") (pin "8") (pinfunction "1_8") (pintype "passive"))
    )
    (net (code "5") (name "3V_REF") (class "Default")
      (node (ref "C20") (pin "1") (pinfunction "1_1") (pintype "passive"))
      (node (ref "IC9") (pin "5") (pinfunction "VOUT_5") (pintype "output"))
      (node (ref "R51") (pin "1") (pinfunction "1_1") (pintype "passive"))
      (node (ref "SW1") (pin "COM") (pinfunction "COM_COM") (pintype "passive"))
    )
    (net (code "6") (name "ABS_SHAPE") (class "Default")
      (node (ref "IC4") (pin "7") (pinfunction "OUT_7") (pintype "output"))
      (node (ref "R24") (pin "2") (pinfunction "2_2") (pintype "passive"))
      (node (ref "R27") (pin "1") (pinfunction "1_1") (pintype "passive"))
    )
    (net (code "7") (name "AP1_P") (class "Default")
      (node (ref "IC4") (pin "14") (pinfunction "OUT_14") (pintype "output"))
      (node (ref "IC6") (pin "3") (pinfunction "IN-_3") (pintype "input"))
      (node (ref "R31") (pin "1") (pinfunction "1_1") (pintype "passive"))
      (node (ref "R32") (pin "1") (pinfunction "1_1") (pintype "passive"))
      (node (ref "R38") (pin "2") (pinfunction "2_2") (pintype "passive"))
    )
    (net (code "8") (name "COMP_BUFF") (class "Default")
      (node (ref "IC3") (pin "1") (pinfunction "OUT_1") (pintype "output"))
      (node (ref "IC3") (pin "2") (pinfunction "-IN_2") (pintype "input"))
      (node (ref "X1") (pin "10") (pinfunction "1_10") (pintype "passive"))
    )
    (net (code "9") (name "COMP_OUT") (class "Default")
      (node (ref "IC3") (pin "3") (pinfunction "+IN_3") (pintype "input"))
      (node (ref "IC6") (pin "7") (pinfunction "COL_OUT_7") (pintype "bidirectional"))
      (node (ref "IC8") (pin "1") (pinfunction "IN_1") (pintype "input"))
      (node (ref "IC8") (pin "8") (pinfunction "IN_8") (pintype "input"))
      (node (ref "R36") (pin "1") (pinfunction "1_1") (pintype "passive"))
      (node (ref "R62") (pin "2") (pinfunction "2_2") (pintype "passive"))
    )
    (net (code "10") (name "FREQ_IN_1") (class "Default")
      (node (ref "R11") (pin "2") (pinfunction "2_2") (pintype "passive"))
      (node (ref "X1") (pin "1") (pinfunction "1_1") (pintype "passive"))
    )
    (net (code "11") (name "FREQ_IN_2") (class "Default")
      (node (ref "RV2") (pin "3") (pinfunction "E_3") (pintype "passive"))
      (node (ref "X1") (pin "3") (pinfunction "1_3") (pintype "passive"))
    )
    (net (code "12") (name "F_CV_POSTDIV") (class "Default")
      (node (ref "IC5") (pin "9") (pinfunction "B_9") (pintype "passive"))
      (node (ref "R41") (pin "1") (pinfunction "1_1") (pintype "passive"))
      (node (ref "R59") (pin "1") (pinfunction "1_1") (pintype "passive"))
    )
    (net (code "13") (name "F_CV_PREDIV") (class "Default")
      (node (ref "IC1") (pin "8") (pinfunction "OUT_8") (pintype "output"))
      (node (ref "R41") (pin "2") (pinfunction "2_2") (pintype "passive"))
      (node (ref "RV6") (pin "2") (pinfunction "S_2") (pintype "passive"))
    )
    (net (code "14") (name "GND") (class "Default")
      (node (ref "C10") (pin "1") (pinfunction "1_1") (pintype "passive"))
      (node (ref "C11") (pin "2") (pinfunction "2_2") (pintype "passive"))
      (node (ref "C12") (pin "1") (pinfunction "1_1") (pintype "passive"))
      (node (ref "C13") (pin "2") (pinfunction "2_2") (pintype "passive"))
      (node (ref "C14") (pin "2") (pinfunction "2_2") (pintype "passive"))
      (node (ref "C15") (pin "1") (pinfunction "1_1") (pintype "passive"))
      (node (ref "C16") (pin "2") (pinfunction "2_2") (pintype "passive"))
      (node (ref "C17") (pin "-") (pinfunction "-_-") (pintype "passive"))
      (node (ref "C18") (pin "+") (pinfunction "+_+") (pintype "passive"))
      (node (ref "C19") (pin "+") (pinfunction "+_+") (pintype "passive"))
      (node (ref "C20") (pin "2") (pinfunction "2_2") (pintype "passive"))
      (node (ref "C4") (pin "2") (pinfunction "2_2") (pintype "passive"))
      (node (ref "C5") (pin "2") (pinfunction "2_2") (pintype "passive"))
      (node (ref "C6") (pin "1") (pinfunction "1_1") (pintype "passive"))
      (node (ref "C7") (pin "2") (pinfunction "2_2") (pintype "passive"))
      (node (ref "C8") (pin "1") (pinfunction "1_1") (pintype "passive"))
      (node (ref "C9") (pin "2") (pinfunction "2_2") (pintype "passive"))
      (node (ref "D3") (pin "A") (pinfunction "A_A") (pintype "passive"))
      (node (ref "IC1") (pin "10") (pinfunction "+IN_10") (pintype "input"))
      (node (ref "IC1") (pin "12") (pinfunction "+IN_12") (pintype "input"))
      (node (ref "IC1") (pin "3") (pinfunction "+IN_3") (pintype "input"))
      (node (ref "IC1") (pin "5") (pinfunction "+IN_5") (pintype "input"))
      (node (ref "IC2") (pin "10") (pinfunction "+IN_10") (pintype "input"))
      (node (ref "IC3") (pin "10") (pinfunction "+IN_10") (pintype "input"))
      (node (ref "IC3") (pin "12") (pinfunction "+IN_12") (pintype "input"))
      (node (ref "IC3") (pin "5") (pinfunction "+IN_5") (pintype "input"))
      (node (ref "IC4") (pin "10") (pinfunction "+IN_10") (pintype "input"))
      (node (ref "IC4") (pin "12") (pinfunction "+IN_12") (pintype "input"))
      (node (ref "IC4") (pin "3") (pinfunction "+IN_3") (pintype "input"))
      (node (ref "IC5") (pin "11") (pinfunction "SUB_11") (pintype "passive"))
      (node (ref "IC5") (pin "12") (pinfunction "E_12") (pintype "passive"))
      (node (ref "IC5") (pin "13") (pinfunction "B_13") (pintype "passive"))
      (node (ref "IC5") (pin "14") (pinfunction "C_14") (pintype "passive"))
      (node (ref "IC5") (pin "2") (pinfunction "B_2") (pintype "passive"))
      (node (ref "IC5") (pin "4") (pinfunction "SUB_4") (pintype "passive"))
      (node (ref "IC5") (pin "6") (pinfunction "B_6") (pintype "passive"))
      (node (ref "IC6") (pin "1") (pinfunction "EMIT_OUT_1") (pintype "bidirectional"))
      (node (ref "IC7") (pin "8") (pinfunction "C_8") (pintype "passive"))
      (node (ref "IC8") (pin "10") (pinfunction "D_10") (pintype "bidirectional"))
      (node (ref "IC8") (pin "11") (pinfunction "S_11") (pintype "bidirectional"))
      (node (ref "IC8") (pin "14") (pinfunction "S_14") (pintype "bidirectional"))
      (node (ref "IC8") (pin "15") (pinfunction "D_15") (pintype "bidirectional"))
      (node (ref "IC8") (pin "16") (pinfunction "IN_16") (pintype "input"))
      (node (ref "IC8") (pin "3") (pinfunction "S_3") (pintype "bidirectional"))
      (node (ref "IC8") (pin "5") (pinfunction "GND_5") (pintype "power_in"))
      (node (ref "IC8") (pin "6") (pinfunction "S_6") (pintype "bidirectional"))
      (node (ref "IC8") (pin "9") (pinfunction "IN_9") (pintype "input"))
      (node (ref "IC9") (pin "2") (pinfunction "GND_2") (pintype "power_in"))
      (node (ref "Q11") (pin "2") (pinfunction "E_2") (pintype "passive"))
      (node (ref "R1") (pin "2") (pinfunction "2_2") (pintype "passive"))
      (node (ref "R13") (pin "2") (pinfunction "2_2") (pintype "passive"))
      (node (ref "R15") (pin "2") (pinfunction "2_2") (pintype "passive"))
      (node (ref "R2") (pin "2") (pinfunction "2_2") (pintype "passive"))
      (node (ref "R3") (pin "2") (pinfunction "2_2") (pintype "passive"))
      (node (ref "R39") (pin "1") (pinfunction "1_1") (pintype "passive"))
      (node (ref "R4") (pin "2") (pinfunction "2_2") (pintype "passive"))
      (node (ref "R60") (pin "2") (pinfunction "2_2") (pintype "passive"))
      (node (ref "R61") (pin "1") (pinfunction "1_1") (pintype "passive"))
      (node (ref "RV2") (pin "1") (pinfunction "A_1") (pintype "passive"))
      (node (ref "RV4") (pin "1") (pinfunction "A_1") (pintype "passive"))
      (node (ref "SV1") (pin "3") (pinfunction "3_3") (pintype "passive"))
      (node (ref "SV1") (pin "4") (pinfunction "4_4") (pintype "passive"))
      (node (ref "SV1") (pin "5") (pinfunction "5_5") (pintype "passive"))
      (node (ref "SV1") (pin "6") (pinfunction "6_6") (pintype "passive"))
      (node (ref "SV1") (pin "7") (pinfunction "7_7") (pintype "passive"))
      (node (ref "SV1") (pin "8") (pinfunction "8_8") (pintype "passive"))
      (node (ref "TP1") (pin "TP") (pinfunction "TP_TP") (pintype "input"))
      (node (ref "X1") (pin "7") (pinfunction "1_7") (pintype "passive"))
    )
    (net (code "15") (name "IN") (class "Default")
      (node (ref "C3") (pin "1") (pinfunction "1_1") (pintype "passive"))
      (node (ref "IC1") (pin "7") (pinfunction "OUT_7") (pintype "output"))
      (node (ref "R20") (pin "1") (pinfunction "1_1") (pintype "passive"))
      (node (ref "R35") (pin "1") (pinfunction "1_1") (pintype "passive"))
      (node (ref "R40") (pin "2") (pinfunction "2_2") (pintype "passive"))
      (node (ref "R7") (pin "2") (pinfunction "2_2") (pintype "passive"))
      (node (ref "TP2") (pin "TP") (pinfunction "TP_TP") (pintype "input"))
    )
    (net (code "16") (name "I_F1") (class "Default")
      (node (ref "Q5") (pin "4") (pinfunction "E_4") (pintype "passive"))
      (node (ref "Q5") (pin "5") (pinfunction "E_5") (pintype "passive"))
      (node (ref "R57") (pin "1") (pinfunction "1_1") (pintype "passive"))
    )
    (net (code "17") (name "I_F2") (class "Default")
      (node (ref "Q6") (pin "4") (pinfunction "E_4") (pintype "passive"))
      (node (ref "Q6") (pin "5") (pinfunction "E_5") (pintype "passive"))
      (node (ref "R58") (pin "1") (pinfunction "1_1") (pintype "passive"))
    )
    (net (code "18") (name "LIN_FM") (class "Default")
      (node (ref "R15") (pin "1") (pinfunction "1_1") (pintype "passive"))
      (node (ref "R52") (pin "1") (pinfunction "1_1") (pintype "passive"))
      (node (ref "X1") (pin "2") (pinfunction "1_2") (pintype "passive"))
    )
    (net (code "19") (name "Net-(D1-PadA)") (class "Default")
      (node (ref "D1") (pin "A") (pinfunction "A_A") (pintype "passive"))
      (node (ref "SV1") (pin "10") (pinfunction "10_10") (pintype "passive"))
      (node (ref "SV1") (pin "9") (pinfunction "9_9") (pintype "passive"))
    )
    (net (code "20") (name "Net-(D2-PadC)") (class "Default")
      (node (ref "D2") (pin "C") (pinfunction "C_C") (pintype "passive"))
      (node (ref "SV1") (pin "1") (pinfunction "1_1") (pintype "passive"))
      (node (ref "SV1") (pin "2") (pinfunction "2_2") (pintype "passive"))
    )
    (net (code "21") (name "Net-(D4-PadA)") (class "Default")
      (node (ref "D4") (pin "A") (pinfunction "A_A") (pintype "passive"))
      (node (ref "R54") (pin "1") (pinfunction "1_1") (pintype "passive"))
    )
    (net (code "22") (name "Net-(D5-PadA)") (class "Default")
      (node (ref "D5") (pin "A") (pinfunction "A_A") (pintype "passive"))
      (node (ref "D6") (pin "A") (pinfunction "A_A") (pintype "passive"))
      (node (ref "R35") (pin "2") (pinfunction "2_2") (pintype "passive"))
    )
    (net (code "23") (name "Net-(D6-PadC)") (class "Default")
      (node (ref "D6") (pin "C") (pinfunction "C_C") (pintype "passive"))
      (node (ref "R42") (pin "1") (pinfunction "1_1") (pintype "passive"))
    )
    (net (code "24") (name "Net-(IC1A--IN)") (class "Default")
      (node (ref "C1") (pin "2") (pinfunction "2_2") (pintype "passive"))
      (node (ref "D5") (pin "C") (pinfunction "C_C") (pintype "passive"))
      (node (ref "IC1") (pin "2") (pinfunction "-IN_2") (pintype "input"))
      (node (ref "R49") (pin "1") (pinfunction "1_1") (pintype "passive"))
    )
    (net (code "25") (name "Net-(IC1A-OUT)") (class "Default")
      (node (ref "C1") (pin "1") (pinfunction "1_1") (pintype "passive"))
      (node (ref "IC1") (pin "1") (pinfunction "OUT_1") (pintype "output"))
      (node (ref "R48") (pin "1") (pinfunction "1_1") (pintype "passive"))
      (node (ref "R49") (pin "2") (pinfunction "2_2") (pintype "passive"))
    )
    (net (code "26") (name "Net-(IC1B--IN)") (class "Default")
      (node (ref "IC1") (pin "6") (pinfunction "-IN_6") (pintype "input"))
      (node (ref "Q12") (pin "2") (pinfunction "S_2") (pintype "passive"))
      (node (ref "R40") (pin "1") (pinfunction "1_1") (pintype "passive"))
    )
    (net (code "27") (name "Net-(IC1C--IN)") (class "Default")
      (node (ref "IC1") (pin "9") (pinfunction "-IN_9") (pintype "input"))
      (node (ref "R11") (pin "1") (pinfunction "1_1") (pintype "passive"))
      (node (ref "R12") (pin "1") (pinfunction "1_1") (pintype "passive"))
      (node (ref "R17") (pin "1") (pinfunction "1_1") (pintype "passive"))
      (node (ref "R18") (pin "1") (pinfunction "1_1") (pintype "passive"))
      (node (ref "R19") (pin "1") (pinfunction "1_1") (pintype "passive"))
      (node (ref "R43") (pin "2") (pinfunction "2_2") (pintype "passive"))
      (node (ref "R50") (pin "1") (pinfunction "1_1") (pintype "passive"))
    )
    (net (code "28") (name "Net-(IC1D--IN)") (class "Default")
      (node (ref "IC1") (pin "13") (pinfunction "-IN_13") (pintype "input"))
      (node (ref "IC5") (pin "8") (pinfunction "C_8") (pintype "passive"))
      (node (ref "R51") (pin "2") (pinfunction "2_2") (pintype "passive"))
      (node (ref "R52") (pin "2") (pinfunction "2_2") (pintype "passive"))
    )
    (net (code "29") (name "Net-(IC1D-OUT)") (class "Default")
      (node (ref "IC1") (pin "14") (pinfunction "OUT_14") (pintype "output"))
      (node (ref "R55") (pin "2") (pinfunction "2_2") (pintype "passive"))
    )
    (net (code "30") (name "Net-(IC2A-+IN)") (class "Default")
      (node (ref "IC2") (pin "3") (pinfunction "+IN_3") (pintype "input"))
      (node (ref "IC8") (pin "2") (pinfunction "D_2") (pintype "bidirectional"))
      (node (ref "R32") (pin "2") (pinfunction "2_2") (pintype "passive"))
    )
    (net (code "31") (name "Net-(IC2A--IN)") (class "Default")
      (node (ref "IC2") (pin "2") (pinfunction "-IN_2") (pintype "input"))
      (node (ref "R30") (pin "1") (pinfunction "1_1") (pintype "passive"))
      (node (ref "R31") (pin "2") (pinfunction "2_2") (pintype "passive"))
    )
    (net (code "32") (name "Net-(IC2A-OUT)") (class "Default")
      (node (ref "IC2") (pin "1") (pinfunction "OUT_1") (pintype "output"))
      (node (ref "R29") (pin "1") (pinfunction "1_1") (pintype "passive"))
      (node (ref "R30") (pin "2") (pinfunction "2_2") (pintype "passive"))
    )
    (net (code "33") (name "Net-(IC2B-+IN)") (class "Default")
      (node (ref "C21") (pin "2") (pinfunction "2_2") (pintype "passive"))
      (node (ref "IC2") (pin "5") (pinfunction "+IN_5") (pintype "input"))
      (node (ref "R39") (pin "2") (pinfunction "2_2") (pintype "passive"))
    )
    (net (code "34") (name "Net-(IC2B--IN)") (class "Default")
      (node (ref "IC2") (pin "6") (pinfunction "-IN_6") (pintype "input"))
      (node (ref "IC2") (pin "7") (pinfunction "OUT_7") (pintype "output"))
      (node (ref "R21") (pin "1") (pinfunction "1_1") (pintype "passive"))
      (node (ref "R22") (pin "1") (pinfunction "1_1") (pintype "passive"))
    )
    (net (code "35") (name "Net-(IC2C--IN)") (class "Default")
      (node (ref "IC2") (pin "9") (pinfunction "-IN_9") (pintype "input"))
      (node (ref "R27") (pin "2") (pinfunction "2_2") (pintype "passive"))
      (node (ref "R28") (pin "1") (pinfunction "1_1") (pintype "passive"))
      (node (ref "R29") (pin "2") (pinfunction "2_2") (pintype "passive"))
    )
    (net (code "36") (name "Net-(IC2D-+IN)") (class "Default")
      (node (ref "IC2") (pin "12") (pinfunction "+IN_12") (pintype "input"))
      (node (ref "IC8") (pin "7") (pinfunction "D_7") (pintype "bidirectional"))
      (node (ref "R22") (pin "2") (pinfunction "2_2") (pintype "passive"))
    )
    (net (code "37") (name "Net-(IC2D--IN)") (class "Default")
      (node (ref "IC2") (pin "13") (pinfunction "-IN_13") (pintype "input"))
      (node (ref "R21") (pin "2") (pinfunction "2_2") (pintype "passive"))
      (node (ref "R23") (pin "1") (pinfunction "1_1") (pintype "passive"))
    )
    (net (code "38") (name "Net-(IC3B--IN)") (class "Default")
      (node (ref "IC3") (pin "6") (pinfunction "-IN_6") (pintype "input"))
      (node (ref "IC3") (pin "7") (pinfunction "OUT_7") (pintype "output"))
    )
    (net (code "39") (name "Net-(IC3C--IN)") (class "Default")
      (node (ref "IC3") (pin "8") (pinfunction "OUT_8") (pintype "output"))
      (node (ref "IC3") (pin "9") (pinfunction "-IN_9") (pintype "input"))
    )
    (net (code "40") (name "Net-(IC3D--IN)") (class "Default")
      (node (ref "IC3") (pin "13") (pinfunction "-IN_13") (pintype "input"))
      (node (ref "R33") (pin "1") (pinfunction "1_1") (pintype "passive"))
      (node (ref "R34") (pin "2") (pinfunction "2_2") (pintype "passive"))
    )
    (net (code "41") (name "Net-(IC4A--IN)") (class "Default")
      (node (ref "D7") (pin "C") (pinfunction "C_C") (pintype "passive"))
      (node (ref "IC4") (pin "2") (pinfunction "-IN_2") (pintype "input"))
      (node (ref "IC4") (pin "5") (pinfunction "+IN_5") (pintype "input"))
      (node (ref "R26") (pin "2") (pinfunction "2_2") (pintype "passive"))
    )
    (net (code "42") (name "Net-(IC4A-OUT)") (class "Default")
      (node (ref "D7") (pin "A") (pinfunction "A_A") (pintype "passive"))
      (node (ref "IC4") (pin "1") (pinfunction "OUT_1") (pintype "output"))
    )
    (net (code "43") (name "Net-(IC4B--IN)") (class "Default")
      (node (ref "IC4") (pin "6") (pinfunction "-IN_6") (pintype "input"))
      (node (ref "R24") (pin "1") (pinfunction "1_1") (pintype "passive"))
      (node (ref "R25") (pin "2") (pinfunction "2_2") (pintype "passive"))
    )
    (net (code "44") (name "Net-(IC4C--IN)") (class "Default")
      (node (ref "IC4") (pin "9") (pinfunction "-IN_9") (pintype "input"))
      (node (ref "R16") (pin "1") (pinfunction "1_1") (pintype "passive"))
      (node (ref "R44") (pin "2") (pinfunction "2_2") (pintype "passive"))
      (node (ref "R46") (pin "2") (pinfunction "2_2") (pintype "passive"))
    )
    (net (code "45") (name "Net-(IC4D--IN)") (class "Default")
      (node (ref "IC4") (pin "13") (pinfunction "-IN_13") (pintype "input"))
      (node (ref "R20") (pin "2") (pinfunction "2_2") (pintype "passive"))
      (node (ref "R37") (pin "2") (pinfunction "2_2") (pintype "passive"))
      (node (ref "R38") (pin "1") (pinfunction "1_1") (pintype "passive"))
    )
    (net (code "46") (name "Net-(IC5B-C)") (class "Default")
      (node (ref "IC5") (pin "1") (pinfunction "C_1") (pintype "passive"))
      (node (ref "R58") (pin "2") (pinfunction "2_2") (pintype "passive"))
    )
    (net (code "47") (name "Net-(IC5B-E)") (class "Default")
      (node (ref "IC5") (pin "10") (pinfunction "E_10") (pintype "passive"))
      (node (ref "IC5") (pin "3") (pinfunction "E_3") (pintype "passive"))
      (node (ref "IC5") (pin "5") (pinfunction "E_5") (pintype "passive"))
      (node (ref "R55") (pin "1") (pinfunction "1_1") (pintype "passive"))
    )
    (net (code "48") (name "Net-(IC5D-C)") (class "Default")
      (node (ref "IC5") (pin "7") (pinfunction "C_7") (pintype "passive"))
      (node (ref "R57") (pin "2") (pinfunction "2_2") (pintype "passive"))
    )
    (net (code "49") (name "Net-(IC6-IN+)") (class "Default")
      (node (ref "IC6") (pin "2") (pinfunction "IN+_2") (pintype "input"))
      (node (ref "R61") (pin "2") (pinfunction "2_2") (pintype "passive"))
      (node (ref "R62") (pin "1") (pinfunction "1_1") (pintype "passive"))
    )
    (net (code "50") (name "Net-(Q1A-B)") (class "Default")
      (node (ref "Q1") (pin "1") (pinfunction "B_1") (pintype "passive"))
      (node (ref "Q1") (pin "2") (pinfunction "B_2") (pintype "passive"))
      (node (ref "Q1") (pin "3") (pinfunction "C_3") (pintype "passive"))
      (node (ref "Q3") (pin "2") (pinfunction "E_2") (pintype "passive"))
    )
    (net (code "51") (name "Net-(Q1A-C)") (class "Default")
      (node (ref "Q1") (pin "6") (pinfunction "C_6") (pintype "passive"))
      (node (ref "Q3") (pin "1") (pinfunction "B_1") (pintype "passive"))
      (node (ref "Q5") (pin "3") (pinfunction "C_3") (pintype "passive"))
    )
    (net (code "52") (name "Net-(Q2A-B)") (class "Default")
      (node (ref "Q2") (pin "1") (pinfunction "B_1") (pintype "passive"))
      (node (ref "Q2") (pin "2") (pinfunction "B_2") (pintype "passive"))
      (node (ref "Q2") (pin "3") (pinfunction "C_3") (pintype "passive"))
      (node (ref "Q4") (pin "2") (pinfunction "E_2") (pintype "passive"))
    )
    (net (code "53") (name "Net-(Q2A-C)") (class "Default")
      (node (ref "Q2") (pin "6") (pinfunction "C_6") (pintype "passive"))
      (node (ref "Q4") (pin "1") (pinfunction "B_1") (pintype "passive"))
      (node (ref "Q6") (pin "3") (pinfunction "C_3") (pintype "passive"))
    )
    (net (code "54") (name "Net-(Q3-C)") (class "Default")
      (node (ref "C3") (pin "2") (pinfunction "2_2") (pintype "passive"))
      (node (ref "Q3") (pin "3") (pinfunction "C_3") (pintype "passive"))
      (node (ref "Q5") (pin "6") (pinfunction "C_6") (pintype "passive"))
      (node (ref "Q7") (pin "1") (pinfunction "B_1") (pintype "passive"))
    )
    (net (code "55") (name "Net-(Q5A-B)") (class "Default")
      (node (ref "Q5") (pin "1") (pinfunction "B_1") (pintype "passive"))
      (node (ref "R2") (pin "1") (pinfunction "1_1") (pintype "passive"))
      (node (ref "R7") (pin "1") (pinfunction "1_1") (pintype "passive"))
      (node (ref "R8") (pin "2") (pinfunction "2_2") (pintype "passive"))
    )
    (net (code "56") (name "Net-(Q5B-B)") (class "Default")
      (node (ref "Q5") (pin "2") (pinfunction "B_2") (pintype "passive"))
      (node (ref "R1") (pin "1") (pinfunction "1_1") (pintype "passive"))
    )
    (net (code "57") (name "Net-(Q6A-B)") (class "Default")
      (node (ref "Q6") (pin "1") (pinfunction "B_1") (pintype "passive"))
      (node (ref "R10") (pin "2") (pinfunction "2_2") (pintype "passive"))
      (node (ref "R4") (pin "1") (pinfunction "1_1") (pintype "passive"))
      (node (ref "R9") (pin "1") (pinfunction "1_1") (pintype "passive"))
    )
    (net (code "58") (name "Net-(Q6B-B)") (class "Default")
      (node (ref "Q6") (pin "2") (pinfunction "B_2") (pintype "passive"))
      (node (ref "R3") (pin "1") (pinfunction "1_1") (pintype "passive"))
    )
    (net (code "59") (name "Net-(Q7-E)") (class "Default")
      (node (ref "Q7") (pin "2") (pinfunction "E_2") (pintype "passive"))
      (node (ref "Q8") (pin "1") (pinfunction "B_1") (pintype "passive"))
    )
    (net (code "60") (name "Net-(Q10-B)") (class "Default")
      (node (ref "Q10") (pin "1") (pinfunction "B_1") (pintype "passive"))
      (node (ref "Q9") (pin "2") (pinfunction "E_2") (pintype "passive"))
    )
    (net (code "61") (name "Net-(Q11-B)") (class "Default")
      (node (ref "D3") (pin "C") (pinfunction "C_C") (pintype "passive"))
      (node (ref "Q11") (pin "1") (pinfunction "B_1") (pintype "passive"))
      (node (ref "R13") (pin "1") (pinfunction "1_1") (pintype "passive"))
      (node (ref "R45") (pin "2") (pinfunction "2_2") (pintype "passive"))
    )
    (net (code "62") (name "Net-(Q11-C)") (class "Default")
      (node (ref "D4") (pin "C") (pinfunction "C_C") (pintype "passive"))
      (node (ref "Q11") (pin "3") (pinfunction "C_3") (pintype "passive"))
      (node (ref "R14") (pin "1") (pinfunction "1_1") (pintype "passive"))
    )
    (net (code "63") (name "Net-(Q12-D)") (class "Default")
      (node (ref "Q12") (pin "1") (pinfunction "D_1") (pintype "passive"))
      (node (ref "R47") (pin "2") (pinfunction "2_2") (pintype "passive"))
      (node (ref "R56") (pin "2") (pinfunction "2_2") (pintype "passive"))
    )
    (net (code "64") (name "Net-(Q12-G)") (class "Default")
      (node (ref "Q12") (pin "3") (pinfunction "G_3") (pintype "passive"))
      (node (ref "R47") (pin "1") (pinfunction "1_1") (pintype "passive"))
      (node (ref "R48") (pin "2") (pinfunction "2_2") (pintype "passive"))
    )
    (net (code "65") (name "Net-(R17-Pad2)") (class "Default")
      (node (ref "R17") (pin "2") (pinfunction "2_2") (pintype "passive"))
      (node (ref "SW1") (pin "3") (pinfunction "3_3") (pintype "passive"))
    )
    (net (code "66") (name "Net-(R18-Pad2)") (class "Default")
      (node (ref "R18") (pin "2") (pinfunction "2_2") (pintype "passive"))
      (node (ref "SW1") (pin "2") (pinfunction "2_2") (pintype "passive"))
    )
    (net (code "67") (name "Net-(R19-Pad2)") (class "Default")
      (node (ref "R19") (pin "2") (pinfunction "2_2") (pintype "passive"))
      (node (ref "SW1") (pin "1") (pinfunction "1_1") (pintype "passive"))
    )
    (net (code "68") (name "Net-(R59-Pad2)") (class "Default")
      (node (ref "R59") (pin "2") (pinfunction "2_2") (pintype "passive"))
      (node (ref "R60") (pin "1") (pinfunction "1_1") (pintype "passive"))
    )
    (net (code "69") (name "Net-(RV1-S)") (class "Default")
      (node (ref "R50") (pin "2") (pinfunction "2_2") (pintype "passive"))
      (node (ref "RV1") (pin "2") (pinfunction "S_2") (pintype "passive"))
    )
    (net (code "70") (name "Net-(RV2-S)") (class "Default")
      (node (ref "R12") (pin "2") (pinfunction "2_2") (pintype "passive"))
      (node (ref "RV2") (pin "2") (pinfunction "S_2") (pintype "passive"))
    )
    (net (code "71") (name "Net-(RV3-S)") (class "Default")
      (node (ref "R46") (pin "1") (pinfunction "1_1") (pintype "passive"))
      (node (ref "RV3") (pin "2") (pinfunction "S_2") (pintype "passive"))
    )
    (net (code "72") (name "Net-(RV4-S)") (class "Default")
      (node (ref "R44") (pin "1") (pinfunction "1_1") (pintype "passive"))
      (node (ref "RV4") (pin "2") (pinfunction "S_2") (pintype "passive"))
    )
    (net (code "73") (name "Net-(RV5-A)") (class "Default")
      (node (ref "R42") (pin "2") (pinfunction "2_2") (pintype "passive"))
      (node (ref "RV5") (pin "1") (pinfunction "A_1") (pintype "passive"))
    )
    (net (code "74") (name "Net-(RV6-A)") (class "Default")
      (node (ref "R43") (pin "1") (pinfunction "1_1") (pintype "passive"))
      (node (ref "RV6") (pin "1") (pinfunction "A_1") (pintype "passive"))
    )
    (net (code "75") (name "OUT_1") (class "Default")
      (node (ref "C2") (pin "1") (pinfunction "1_1") (pintype "passive"))
      (node (ref "C21") (pin "1") (pinfunction "1_1") (pintype "passive"))
      (node (ref "Q8") (pin "2") (pinfunction "E_2") (pintype "passive"))
      (node (ref "R5") (pin "1") (pinfunction "1_1") (pintype "passive"))
      (node (ref "R8") (pin "1") (pinfunction "1_1") (pintype "passive"))
      (node (ref "R9") (pin "2") (pinfunction "2_2") (pintype "passive"))
    )
    (net (code "76") (name "OUT_2") (class "Default")
      (node (ref "Q10") (pin "2") (pinfunction "E_2") (pintype "passive"))
      (node (ref "R10") (pin "1") (pinfunction "1_1") (pintype "passive"))
      (node (ref "R56") (pin "1") (pinfunction "1_1") (pintype "passive"))
      (node (ref "R6") (pin "1") (pinfunction "1_1") (pintype "passive"))
    )
    (net (code "77") (name "SAW") (class "Default")
      (node (ref "IC2") (pin "14") (pinfunction "OUT_14") (pintype "output"))
      (node (ref "R23") (pin "2") (pinfunction "2_2") (pintype "passive"))
      (node (ref "X1") (pin "12") (pinfunction "1_12") (pintype "passive"))
    )
    (net (code "78") (name "SHAPE") (class "Default")
      (node (ref "IC4") (pin "8") (pinfunction "OUT_8") (pintype "output"))
      (node (ref "R16") (pin "2") (pinfunction "2_2") (pintype "passive"))
      (node (ref "R25") (pin "1") (pinfunction "1_1") (pintype "passive"))
      (node (ref "R26") (pin "1") (pinfunction "1_1") (pintype "passive"))
      (node (ref "R37") (pin "1") (pinfunction "1_1") (pintype "passive"))
    )
    (net (code "79") (name "SHAPE_IN") (class "Default")
      (node (ref "RV4") (pin "3") (pinfunction "E_3") (pintype "passive"))
      (node (ref "X1") (pin "9") (pinfunction "1_9") (pintype "passive"))
    )
    (net (code "80") (name "TRI") (class "Default")
      (node (ref "IC2") (pin "8") (pinfunction "OUT_8") (pintype "output"))
      (node (ref "R28") (pin "2") (pinfunction "2_2") (pintype "passive"))
      (node (ref "X1") (pin "11") (pinfunction "1_11") (pintype "passive"))
    )
    (net (code "81") (name "XMOD") (class "Default")
      (node (ref "C2") (pin "2") (pinfunction "2_2") (pintype "passive"))
      (node (ref "Q4") (pin "3") (pinfunction "C_3") (pintype "passive"))
      (node (ref "Q6") (pin "6") (pinfunction "C_6") (pintype "passive"))
      (node (ref "Q9") (pin "1") (pinfunction "B_1") (pintype "passive"))
      (node (ref "R54") (pin "2") (pinfunction "2_2") (pintype "passive"))
    )
    (net (code "82") (name "XMOD_IN") (class "Default")
      (node (ref "R45") (pin "1") (pinfunction "1_1") (pintype "passive"))
      (node (ref "X1") (pin "4") (pinfunction "1_4") (pintype "passive"))
    )
    (net (code "83") (name "unconnected-(IC6-BALANCE-Pad5)") (class "Default")
      (node (ref "IC6") (pin "5") (pinfunction "BALANCE_5") (pintype "bidirectional"))
    )
    (net (code "84") (name "unconnected-(IC6-BAL{slash}STRB-Pad6)") (class "Default")
      (node (ref "IC6") (pin "6") (pinfunction "BAL/STRB_6") (pintype "bidirectional"))
    )
    (net (code "85") (name "unconnected-(IC7-ADJ-Pad5)") (class "Default")
      (node (ref "IC7") (pin "5") (pinfunction "ADJ_5") (pintype "input"))
    )
    (net (code "86") (name "unconnected-(IC9-REF-Pad1)") (class "Default")
      (node (ref "IC9") (pin "1") (pinfunction "REF_1") (pintype "no_connect"))
    )
    (net (code "87") (name "unconnected-(RV5-E-Pad3)") (class "Default")
      (node (ref "RV5") (pin "3") (pinfunction "E_3") (pintype "passive"))
    )
    (net (code "88") (name "unconnected-(RV6-E-Pad3)") (class "Default")
      (node (ref "RV6") (pin "3") (pinfunction "E_3") (pintype "passive"))
    )
    (net (code "89") (name "unconnected-(SV1-Pad11)") (class "Default")
      (node (ref "SV1") (pin "11") (pinfunction "11_11") (pintype "passive"))
    )
    (net (code "90") (name "unconnected-(SV1-Pad12)") (class "Default")
      (node (ref "SV1") (pin "12") (pinfunction "12_12") (pintype "passive"))
    )
    (net (code "91") (name "unconnected-(SV1-Pad13)") (class "Default")
      (node (ref "SV1") (pin "13") (pinfunction "13_13") (pintype "passive"))
    )
    (net (code "92") (name "unconnected-(SV1-Pad14)") (class "Default")
      (node (ref "SV1") (pin "14") (pinfunction "14_14") (pintype "passive"))
    )
    (net (code "93") (name "unconnected-(SV1-Pad15)") (class "Default")
      (node (ref "SV1") (pin "15") (pinfunction "15_15") (pintype "passive"))
    )
    (net (code "94") (name "unconnected-(SV1-Pad16)") (class "Default")
      (node (ref "SV1") (pin "16") (pinfunction "16_16") (pintype "passive"))
    )
    (net (code "95") (name "unconnected-(SW1-Pad4)") (class "Default")
      (node (ref "SW1") (pin "4") (pinfunction "4_4") (pintype "passive"))
    )
  )
)
